# Sheet1.net
KiCad netlist of a schematic drawn in Altium Designer
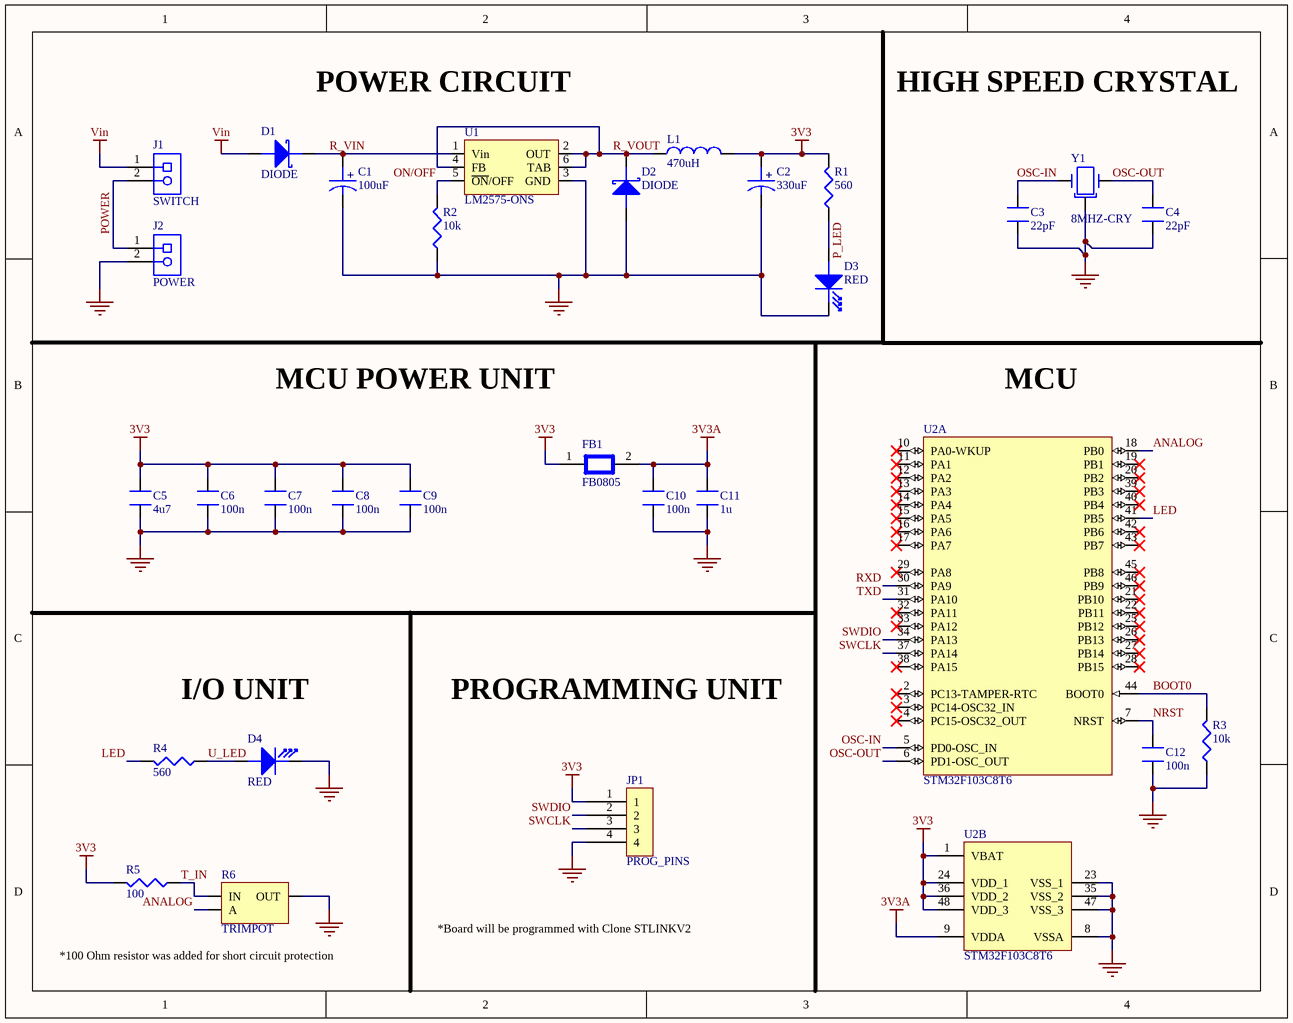
[diagram p0: Sheet1.SchDoc]

(export (version "E")
  (design (tool "Eeschema 10.0.6"))
  (components
    (comp (ref "C1")
      (value "100uF")
      (footprint "10X10-ALCAP")
      (libsource (lib "brain-dll-Sch") (part "10X10-ALCAP"))
    )
    (comp (ref "C2")
      (value "330uF")
      (footprint "10X10-ALCAP")
      (libsource (lib "brain-dll-Sch") (part "10X10-ALCAP"))
    )
    (comp (ref "C3") (value "22pF") (footprint "Z0603") (libsource (lib "brain-dll-Sch") (part "C0603")))
    (comp (ref "C4") (value "22pF") (footprint "Z0603") (libsource (lib "brain-dll-Sch") (part "C0603")))
    (comp (ref "C5") (value "4u7") (footprint "Z0603") (libsource (lib "brain-dll-Sch") (part "C0603")))
    (comp (ref "C6") (value "100n") (footprint "Z0603") (libsource (lib "brain-dll-Sch") (part "C0603")))
    (comp (ref "C7") (value "100n") (footprint "Z0603") (libsource (lib "brain-dll-Sch") (part "C0603")))
    (comp (ref "C8") (value "100n") (footprint "Z0603") (libsource (lib "brain-dll-Sch") (part "C0603")))
    (comp (ref "C9") (value "100n") (footprint "Z0603") (libsource (lib "brain-dll-Sch") (part "C0603")))
    (comp (ref "C10") (value "100n") (footprint "Z0603") (libsource (lib "brain-dll-Sch") (part "C0603")))
    (comp (ref "C11") (value "1u") (footprint "Z0603") (libsource (lib "brain-dll-Sch") (part "C0603")))
    (comp (ref "C12") (value "100n") (footprint "Z0603") (libsource (lib "brain-dll-Sch") (part "C0603")))
    (comp (ref "D1")
      (value "DIODE")
      (footprint "SOD-123")
      (libsource (lib "brain-dll-Sch") (part "D-SOD123"))
    )
    (comp (ref "D2")
      (value "DIODE")
      (footprint "SOD-123")
      (libsource (lib "brain-dll-Sch") (part "D-SOD123"))
    )
    (comp (ref "D3") (value "RED") (footprint "LED-0603") (libsource (lib "brain-dll-Sch") (part "L0603")))
    (comp (ref "D4") (value "RED") (footprint "LED-0603") (libsource (lib "brain-dll-Sch") (part "L0603")))
    (comp (ref "FB1") (value "FB0805") (footprint "C0805") (libsource (lib "brain-dll-Sch") (part "FB0805")))
    (comp (ref "J1")
      (value "SWITCH")
      (footprint "PHOE-1729128-2_V")
      (description "PCB Terminal Block, 13.5 A, 400 V, 2-Pin THD, RoHS, Bulk")
      (libsource (lib "Altium Content Vault") (part "CN-2P-F-R2"))
    )
    (comp (ref "J2")
      (value "POWER")
      (footprint "PHOE-1729128-2_V")
      (description "PCB Terminal Block, 13.5 A, 400 V, 2-Pin THD, RoHS, Bulk")
      (libsource (lib "Altium Content Vault") (part "CN-2P-F-R2"))
    )
    (comp (ref "JP1")
      (value "PROG_PINS")
      (footprint "HDR-1X4-2.54mm")
      (libsource (lib "brain-dll-Sch") (part "1X4MALE"))
    )
    (comp (ref "L1")
      (value "470uH")
      (footprint "10X9-IND")
      (libsource (lib "brain-dll-Sch") (part "10X9-IND"))
    )
    (comp (ref "R1") (value "560") (footprint "R0603") (libsource (lib "brain-dll-Sch") (part "R0603")))
    (comp (ref "R2") (value "10k") (footprint "R0603") (libsource (lib "brain-dll-Sch") (part "R0603")))
    (comp (ref "R3") (value "10k") (footprint "R0603") (libsource (lib "brain-dll-Sch") (part "R0603")))
    (comp (ref "R4") (value "560") (footprint "R0603") (libsource (lib "brain-dll-Sch") (part "R0603")))
    (comp (ref "R5") (value "100") (footprint "R0603") (libsource (lib "brain-dll-Sch") (part "R0603")))
    (comp (ref "R6")
      (value "TRIMPOT")
      (footprint "TRIM-3")
      (libsource (lib "brain-dll-Sch") (part "TRIMPOT"))
    )
    (comp (ref "U1")
      (value "LM2575-ONS")
      (footprint "D2PAK")
      (libsource (lib "brain-dll-Sch") (part "LM2575"))
    )
    (comp (ref "U2")
      (value "STM32F103C8T6")
      (footprint "STM-LQFP48_L")
      (libsource (lib "Altium Content Vault") (part "MC-ARM-STM32F103X8_B-SQ48"))
    )
    (comp (ref "Y1")
      (value "8MHZ-CRY")
      (footprint "4-SMD")
      (libsource (lib "brain-dll-Sch") (part "8MHZ-CRYS-4S"))
    )
  )
  (nets
    (net (code "1") (name "/ANALOG") (class "Default")
      (node (ref "R6") (pin "2") (pinfunction "A_2") (pintype "passive"))
      (node (ref "U2") (pin "18") (pinfunction "PB0_18") (pintype "bidirectional"))
    )
    (net (code "2") (name "/BOOT0") (class "Default")
      (node (ref "R3") (pin "2") (pinfunction "2_2") (pintype "passive"))
      (node (ref "U2") (pin "44") (pinfunction "BOOT0_44") (pintype "input"))
    )
    (net (code "3") (name "/LED") (class "Default")
      (node (ref "R4") (pin "2") (pinfunction "2_2") (pintype "passive"))
      (node (ref "U2") (pin "41") (pinfunction "PB5_41") (pintype "bidirectional"))
    )
    (net (code "4") (name "/NRST") (class "Default")
      (node (ref "C12") (pin "2") (pinfunction "2_2") (pintype "passive"))
      (node (ref "U2") (pin "7") (pinfunction "NRST_7") (pintype "bidirectional"))
    )
    (net (code "5") (name "/ON{slash}OFF") (class "Default")
      (node (ref "R2") (pin "2") (pinfunction "2_2") (pintype "passive"))
      (node (ref "U1") (pin "5") (pinfunction "~{ON}/OFF_5") (pintype "passive"))
    )
    (net (code "6") (name "/OSC-IN") (class "Default")
      (node (ref "C3") (pin "2") (pinfunction "2_2") (pintype "passive"))
      (node (ref "U2") (pin "5") (pinfunction "PD0-OSC_IN_5") (pintype "bidirectional"))
      (node (ref "Y1") (pin "1") (pinfunction "1_1") (pintype "passive"))
    )
    (net (code "7") (name "/OSC-OUT") (class "Default")
      (node (ref "C4") (pin "2") (pinfunction "2_2") (pintype "passive"))
      (node (ref "U2") (pin "6") (pinfunction "PD1-OSC_OUT_6") (pintype "bidirectional"))
      (node (ref "Y1") (pin "3") (pinfunction "3_3") (pintype "passive"))
    )
    (net (code "8") (name "/POWER") (class "Default")
      (node (ref "J1") (pin "2") (pinfunction "2_2") (pintype "passive"))
      (node (ref "J2") (pin "1") (pinfunction "1_1") (pintype "passive"))
    )
    (net (code "9") (name "/P_LED") (class "Default")
      (node (ref "D3") (pin "2") (pinfunction "Anode_2") (pintype "passive"))
      (node (ref "R1") (pin "1") (pinfunction "1_1") (pintype "passive"))
    )
    (net (code "10") (name "/RXD") (class "Default")
      (node (ref "U2") (pin "30") (pinfunction "PA9_30") (pintype "bidirectional"))
    )
    (net (code "11") (name "/R_VIN") (class "Default")
      (node (ref "C1") (pin "1") (pinfunction "1_1") (pintype "passive"))
      (node (ref "D1") (pin "1") (pinfunction "Cathode_1") (pintype "passive"))
      (node (ref "U1") (pin "1") (pinfunction "Vin_1") (pintype "passive"))
    )
    (net (code "12") (name "/R_VOUT") (class "Default")
      (node (ref "D2") (pin "1") (pinfunction "Cathode_1") (pintype "passive"))
      (node (ref "L1") (pin "1") (pinfunction "1_1") (pintype "passive"))
      (node (ref "U1") (pin "2") (pinfunction "OUT_2") (pintype "passive"))
      (node (ref "U1") (pin "4") (pinfunction "FB_4") (pintype "passive"))
      (node (ref "U1") (pin "6") (pinfunction "TAB_6") (pintype "passive"))
    )
    (net (code "13") (name "/SWCLK") (class "Default")
      (node (ref "JP1") (pin "3") (pinfunction "3_3") (pintype "passive"))
      (node (ref "U2") (pin "37") (pinfunction "PA14_37") (pintype "bidirectional"))
    )
    (net (code "14") (name "/SWDIO") (class "Default")
      (node (ref "JP1") (pin "2") (pinfunction "2_2") (pintype "passive"))
      (node (ref "U2") (pin "34") (pinfunction "PA13_34") (pintype "bidirectional"))
    )
    (net (code "15") (name "/TXD") (class "Default")
      (node (ref "U2") (pin "31") (pinfunction "PA10_31") (pintype "bidirectional"))
    )
    (net (code "16") (name "/T_IN") (class "Default")
      (node (ref "R5") (pin "1") (pinfunction "1_1") (pintype "passive"))
      (node (ref "R6") (pin "1") (pinfunction "IN_1") (pintype "passive"))
    )
    (net (code "17") (name "/U_LED") (class "Default")
      (node (ref "D4") (pin "2") (pinfunction "Anode_2") (pintype "passive"))
      (node (ref "R4") (pin "1") (pinfunction "1_1") (pintype "passive"))
    )
    (net (code "18") (name "3V3") (class "Default")
      (node (ref "C2") (pin "1") (pinfunction "1_1") (pintype "passive"))
      (node (ref "C5") (pin "2") (pinfunction "2_2") (pintype "passive"))
      (node (ref "C6") (pin "2") (pinfunction "2_2") (pintype "passive"))
      (node (ref "C7") (pin "2") (pinfunction "2_2") (pintype "passive"))
      (node (ref "C8") (pin "2") (pinfunction "2_2") (pintype "passive"))
      (node (ref "C9") (pin "2") (pinfunction "2_2") (pintype "passive"))
      (node (ref "FB1") (pin "1") (pinfunction "1_1") (pintype "passive"))
      (node (ref "JP1") (pin "1") (pinfunction "1_1") (pintype "passive"))
      (node (ref "L1") (pin "2") (pinfunction "2_2") (pintype "passive"))
      (node (ref "R1") (pin "2") (pinfunction "2_2") (pintype "passive"))
      (node (ref "R5") (pin "2") (pinfunction "2_2") (pintype "passive"))
      (node (ref "U2") (pin "1") (pinfunction "VBAT_1") (pintype "power_in"))
      (node (ref "U2") (pin "24") (pinfunction "VDD_1_24") (pintype "power_in"))
      (node (ref "U2") (pin "36") (pinfunction "VDD_2_36") (pintype "power_in"))
      (node (ref "U2") (pin "48") (pinfunction "VDD_3_48") (pintype "power_in"))
    )
    (net (code "19") (name "3V3A") (class "Default")
      (node (ref "C10") (pin "2") (pinfunction "2_2") (pintype "passive"))
      (node (ref "C11") (pin "2") (pinfunction "2_2") (pintype "passive"))
      (node (ref "FB1") (pin "2") (pinfunction "2_2") (pintype "passive"))
      (node (ref "U2") (pin "9") (pinfunction "VDDA_9") (pintype "power_in"))
    )
    (net (code "20") (name "GND") (class "Default")
      (node (ref "C1") (pin "2") (pinfunction "2_2") (pintype "passive"))
      (node (ref "C10") (pin "1") (pinfunction "1_1") (pintype "passive"))
      (node (ref "C11") (pin "1") (pinfunction "1_1") (pintype "passive"))
      (node (ref "C12") (pin "1") (pinfunction "1_1") (pintype "passive"))
      (node (ref "C2") (pin "2") (pinfunction "2_2") (pintype "passive"))
      (node (ref "C3") (pin "1") (pinfunction "1_1") (pintype "passive"))
      (node (ref "C4") (pin "1") (pinfunction "1_1") (pintype "passive"))
      (node (ref "C5") (pin "1") (pinfunction "1_1") (pintype "passive"))
      (node (ref "C6") (pin "1") (pinfunction "1_1") (pintype "passive"))
      (node (ref "C7") (pin "1") (pinfunction "1_1") (pintype "passive"))
      (node (ref "C8") (pin "1") (pinfunction "1_1") (pintype "passive"))
      (node (ref "C9") (pin "1") (pinfunction "1_1") (pintype "passive"))
      (node (ref "D2") (pin "2") (pinfunction "Anode_2") (pintype "passive"))
      (node (ref "D3") (pin "1") (pinfunction "Cathode_1") (pintype "passive"))
      (node (ref "D4") (pin "1") (pinfunction "Cathode_1") (pintype "passive"))
      (node (ref "J2") (pin "2") (pinfunction "2_2") (pintype "passive"))
      (node (ref "JP1") (pin "4") (pinfunction "4_4") (pintype "passive"))
      (node (ref "R2") (pin "1") (pinfunction "1_1") (pintype "passive"))
      (node (ref "R3") (pin "1") (pinfunction "1_1") (pintype "passive"))
      (node (ref "R6") (pin "3") (pinfunction "OUT_3") (pintype "passive"))
      (node (ref "U1") (pin "3") (pinfunction "GND_3") (pintype "passive"))
      (node (ref "U2") (pin "23") (pinfunction "VSS_1_23") (pintype "power_in"))
      (node (ref "U2") (pin "35") (pinfunction "VSS_2_35") (pintype "power_in"))
      (node (ref "U2") (pin "47") (pinfunction "VSS_3_47") (pintype "power_in"))
      (node (ref "U2") (pin "8") (pinfunction "VSSA_8") (pintype "power_in"))
      (node (ref "Y1") (pin "2") (pinfunction "2_2") (pintype "passive"))
    )
    (net (code "21") (name "Vin") (class "Default")
      (node (ref "D1") (pin "2") (pinfunction "Anode_2") (pintype "passive"))
      (node (ref "J1") (pin "1") (pinfunction "1_1") (pintype "passive"))
    )
    (net (code "22") (name "unconnected-(U2A-PA0-WKUP-Pad10)") (class "Default")
      (node (ref "U2") (pin "10") (pinfunction "PA0-WKUP_10") (pintype "bidirectional+no_connect"))
    )
    (net (code "23") (name "unconnected-(U2A-PA1-Pad11)") (class "Default")
      (node (ref "U2") (pin "11") (pinfunction "PA1_11") (pintype "bidirectional+no_connect"))
    )
    (net (code "24") (name "unconnected-(U2A-PA2-Pad12)") (class "Default")
      (node (ref "U2") (pin "12") (pinfunction "PA2_12") (pintype "bidirectional+no_connect"))
    )
    (net (code "25") (name "unconnected-(U2A-PA3-Pad13)") (class "Default")
      (node (ref "U2") (pin "13") (pinfunction "PA3_13") (pintype "bidirectional+no_connect"))
    )
    (net (code "26") (name "unconnected-(U2A-PA4-Pad14)") (class "Default")
      (node (ref "U2") (pin "14") (pinfunction "PA4_14") (pintype "bidirectional+no_connect"))
    )
    (net (code "27") (name "unconnected-(U2A-PA5-Pad15)") (class "Default")
      (node (ref "U2") (pin "15") (pinfunction "PA5_15") (pintype "bidirectional+no_connect"))
    )
    (net (code "28") (name "unconnected-(U2A-PA6-Pad16)") (class "Default")
      (node (ref "U2") (pin "16") (pinfunction "PA6_16") (pintype "bidirectional+no_connect"))
    )
    (net (code "29") (name "unconnected-(U2A-PA7-Pad17)") (class "Default")
      (node (ref "U2") (pin "17") (pinfunction "PA7_17") (pintype "bidirectional+no_connect"))
    )
    (net (code "30") (name "unconnected-(U2A-PA8-Pad29)") (class "Default")
      (node (ref "U2") (pin "29") (pinfunction "PA8_29") (pintype "bidirectional+no_connect"))
    )
    (net (code "31") (name "unconnected-(U2A-PA11-Pad32)") (class "Default")
      (node (ref "U2") (pin "32") (pinfunction "PA11_32") (pintype "bidirectional+no_connect"))
    )
    (net (code "32") (name "unconnected-(U2A-PA12-Pad33)") (class "Default")
      (node (ref "U2") (pin "33") (pinfunction "PA12_33") (pintype "bidirectional+no_connect"))
    )
    (net (code "33") (name "unconnected-(U2A-PA15-Pad38)") (class "Default")
      (node (ref "U2") (pin "38") (pinfunction "PA15_38") (pintype "bidirectional+no_connect"))
    )
    (net (code "34") (name "unconnected-(U2A-PB1-Pad19)") (class "Default")
      (node (ref "U2") (pin "19") (pinfunction "PB1_19") (pintype "bidirectional+no_connect"))
    )
    (net (code "35") (name "unconnected-(U2A-PB2-Pad20)") (class "Default")
      (node (ref "U2") (pin "20") (pinfunction "PB2_20") (pintype "bidirectional+no_connect"))
    )
    (net (code "36") (name "unconnected-(U2A-PB3-Pad39)") (class "Default")
      (node (ref "U2") (pin "39") (pinfunction "PB3_39") (pintype "bidirectional+no_connect"))
    )
    (net (code "37") (name "unconnected-(U2A-PB4-Pad40)") (class "Default")
      (node (ref "U2") (pin "40") (pinfunction "PB4_40") (pintype "bidirectional+no_connect"))
    )
    (net (code "38") (name "unconnected-(U2A-PB6-Pad42)") (class "Default")
      (node (ref "U2") (pin "42") (pinfunction "PB6_42") (pintype "bidirectional+no_connect"))
    )
    (net (code "39") (name "unconnected-(U2A-PB7-Pad43)") (class "Default")
      (node (ref "U2") (pin "43") (pinfunction "PB7_43") (pintype "bidirectional+no_connect"))
    )
    (net (code "40") (name "unconnected-(U2A-PB8-Pad45)") (class "Default")
      (node (ref "U2") (pin "45") (pinfunction "PB8_45") (pintype "bidirectional+no_connect"))
    )
    (net (code "41") (name "unconnected-(U2A-PB9-Pad46)") (class "Default")
      (node (ref "U2") (pin "46") (pinfunction "PB9_46") (pintype "bidirectional+no_connect"))
    )
    (net (code "42") (name "unconnected-(U2A-PB10-Pad21)") (class "Default")
      (node (ref "U2") (pin "21") (pinfunction "PB10_21") (pintype "bidirectional+no_connect"))
    )
    (net (code "43") (name "unconnected-(U2A-PB11-Pad22)") (class "Default")
      (node (ref "U2") (pin "22") (pinfunction "PB11_22") (pintype "bidirectional+no_connect"))
    )
    (net (code "44") (name "unconnected-(U2A-PB12-Pad25)") (class "Default")
      (node (ref "U2") (pin "25") (pinfunction "PB12_25") (pintype "bidirectional+no_connect"))
    )
    (net (code "45") (name "unconnected-(U2A-PB13-Pad26)") (class "Default")
      (node (ref "U2") (pin "26") (pinfunction "PB13_26") (pintype "bidirectional+no_connect"))
    )
    (net (code "46") (name "unconnected-(U2A-PB14-Pad27)") (class "Default")
      (node (ref "U2") (pin "27") (pinfunction "PB14_27") (pintype "bidirectional+no_connect"))
    )
    (net (code "47") (name "unconnected-(U2A-PB15-Pad28)") (class "Default")
      (node (ref "U2") (pin "28") (pinfunction "PB15_28") (pintype "bidirectional+no_connect"))
    )
    (net (code "48") (name "unconnected-(U2A-PC13-TAMPER-RTC-Pad2)") (class "Default")
      (node (ref "U2") (pin "2") (pinfunction "PC13-TAMPER-RTC_2") (pintype "bidirectional+no_connect"))
    )
    (net (code "49") (name "unconnected-(U2A-PC14-OSC32_IN-Pad3)") (class "Default")
      (node (ref "U2") (pin "3") (pinfunction "PC14-OSC32_IN_3") (pintype "bidirectional+no_connect"))
    )
    (net (code "50") (name "unconnected-(U2A-PC15-OSC32_OUT-Pad4)") (class "Default")
      (node (ref "U2") (pin "4") (pinfunction "PC15-OSC32_OUT_4") (pintype "bidirectional+no_connect"))
    )
  )
)
